# osh-2l-cpwg-via75-v2.net
KiCad netlist of a schematic drawn in EAGLE
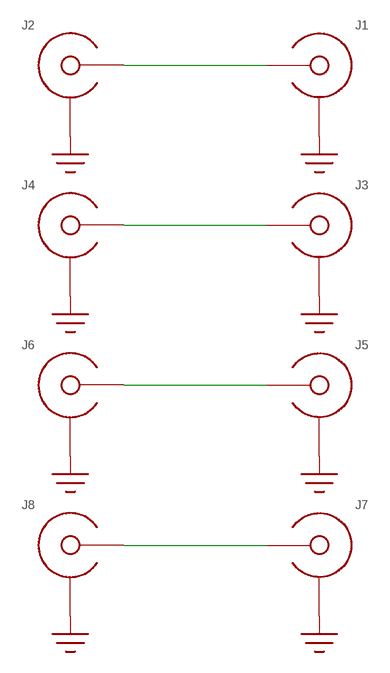
[diagram p0: schematic, sheet 1]

(export (version "E")
  (design (tool "Eeschema 10.0.6"))
  (components
    (comp (ref "J1")
      (value "SMA-EDGE-LAUNCH4020_TAPER")
      (footprint "eagle-import:SMA_EDGE_LAUNCH_2L_4020_TAPER")
      (libsource (lib "eagle-import") (part "SMA-EDGE-LAUNCH4020_TAPER"))
    )
    (comp (ref "J2")
      (value "SMA-EDGE-LAUNCH4020_TAPER")
      (footprint "eagle-import:SMA_EDGE_LAUNCH_2L_4020_TAPER")
      (libsource (lib "eagle-import") (part "yapo_SMA-EDGE-LAUNCH4020_TAPER"))
    )
    (comp (ref "J3")
      (value "SMA-EDGE-LAUNCH4020_TAPER")
      (footprint "eagle-import:SMA_EDGE_LAUNCH_2L_4020_TAPER")
      (libsource (lib "eagle-import") (part "SMA-EDGE-LAUNCH4020_TAPER"))
    )
    (comp (ref "J4")
      (value "SMA-EDGE-LAUNCH4020_TAPER")
      (footprint "eagle-import:SMA_EDGE_LAUNCH_2L_4020_TAPER")
      (libsource (lib "eagle-import") (part "yapo_SMA-EDGE-LAUNCH4020_TAPER"))
    )
    (comp (ref "J5")
      (value "SMA-EDGE-LAUNCH4020_TAPER")
      (footprint "eagle-import:SMA_EDGE_LAUNCH_2L_4020_TAPER")
      (libsource (lib "eagle-import") (part "SMA-EDGE-LAUNCH4020_TAPER"))
    )
    (comp (ref "J6")
      (value "SMA-EDGE-LAUNCH4020_TAPER")
      (footprint "eagle-import:SMA_EDGE_LAUNCH_2L_4020_TAPER")
      (libsource (lib "eagle-import") (part "yapo_SMA-EDGE-LAUNCH4020_TAPER"))
    )
    (comp (ref "J7")
      (value "SMA-EDGE-LAUNCH4020_TAPER")
      (footprint "eagle-import:SMA_EDGE_LAUNCH_2L_4020_TAPER")
      (libsource (lib "eagle-import") (part "SMA-EDGE-LAUNCH4020_TAPER"))
    )
    (comp (ref "J8")
      (value "SMA-EDGE-LAUNCH4020_TAPER")
      (footprint "eagle-import:SMA_EDGE_LAUNCH_2L_4020_TAPER")
      (libsource (lib "eagle-import") (part "yapo_SMA-EDGE-LAUNCH4020_TAPER"))
    )
  )
  (nets
    (net (code "1") (name "GND") (class "Default")
      (node (ref "J1") (pin "BOTTOM_GND") (pinfunction "SHIELD_BOTTOM_GND") (pintype "bidirectional"))
      (node (ref "J1") (pin "GND@1") (pinfunction "SHIELD_GND@1") (pintype "bidirectional"))
      (node (ref "J1") (pin "GND@14") (pinfunction "SHIELD_GND@14") (pintype "bidirectional"))
      (node (ref "J1") (pin "GND@15") (pinfunction "SHIELD_GND@15") (pintype "bidirectional"))
      (node (ref "J1") (pin "GND@16") (pinfunction "SHIELD_GND@16") (pintype "bidirectional"))
      (node (ref "J1") (pin "GND@17") (pinfunction "SHIELD_GND@17") (pintype "bidirectional"))
      (node (ref "J1") (pin "GND@2") (pinfunction "SHIELD_GND@2") (pintype "bidirectional"))
      (node (ref "J1") (pin "GND@3") (pinfunction "SHIELD_GND@3") (pintype "bidirectional"))
      (node (ref "J1") (pin "GND@4") (pinfunction "SHIELD_GND@4") (pintype "bidirectional"))
      (node (ref "J1") (pin "GND@5") (pinfunction "SHIELD_GND@5") (pintype "bidirectional"))
      (node (ref "J1") (pin "GND@6") (pinfunction "SHIELD_GND@6") (pintype "bidirectional"))
      (node (ref "J1") (pin "GND@7") (pinfunction "SHIELD_GND@7") (pintype "bidirectional"))
      (node (ref "J1") (pin "GND@8") (pinfunction "SHIELD_GND@8") (pintype "bidirectional"))
      (node (ref "J1") (pin "GND_PAD1") (pinfunction "SHIELD_GND_PAD1") (pintype "bidirectional"))
      (node (ref "J1") (pin "GND_PAD2") (pinfunction "SHIELD_GND_PAD2") (pintype "bidirectional"))
      (node (ref "J1") (pin "P$1") (pinfunction "SHIELD_P$1") (pintype "bidirectional"))
      (node (ref "J1") (pin "P$2") (pinfunction "SHIELD_P$2") (pintype "bidirectional"))
      (node (ref "J2") (pin "BOTTOM_GND") (pinfunction "SHIELD_BOTTOM_GND") (pintype "bidirectional"))
      (node (ref "J2") (pin "GND@1") (pinfunction "SHIELD_GND@1") (pintype "bidirectional"))
      (node (ref "J2") (pin "GND@14") (pinfunction "SHIELD_GND@14") (pintype "bidirectional"))
      (node (ref "J2") (pin "GND@15") (pinfunction "SHIELD_GND@15") (pintype "bidirectional"))
      (node (ref "J2") (pin "GND@16") (pinfunction "SHIELD_GND@16") (pintype "bidirectional"))
      (node (ref "J2") (pin "GND@17") (pinfunction "SHIELD_GND@17") (pintype "bidirectional"))
      (node (ref "J2") (pin "GND@2") (pinfunction "SHIELD_GND@2") (pintype "bidirectional"))
      (node (ref "J2") (pin "GND@3") (pinfunction "SHIELD_GND@3") (pintype "bidirectional"))
      (node (ref "J2") (pin "GND@4") (pinfunction "SHIELD_GND@4") (pintype "bidirectional"))
      (node (ref "J2") (pin "GND@5") (pinfunction "SHIELD_GND@5") (pintype "bidirectional"))
      (node (ref "J2") (pin "GND@6") (pinfunction "SHIELD_GND@6") (pintype "bidirectional"))
      (node (ref "J2") (pin "GND@7") (pinfunction "SHIELD_GND@7") (pintype "bidirectional"))
      (node (ref "J2") (pin "GND@8") (pinfunction "SHIELD_GND@8") (pintype "bidirectional"))
      (node (ref "J2") (pin "GND_PAD1") (pinfunction "SHIELD_GND_PAD1") (pintype "bidirectional"))
      (node (ref "J2") (pin "GND_PAD2") (pinfunction "SHIELD_GND_PAD2") (pintype "bidirectional"))
      (node (ref "J2") (pin "P$1") (pinfunction "SHIELD_P$1") (pintype "bidirectional"))
      (node (ref "J2") (pin "P$2") (pinfunction "SHIELD_P$2") (pintype "bidirectional"))
      (node (ref "J3") (pin "BOTTOM_GND") (pinfunction "SHIELD_BOTTOM_GND") (pintype "bidirectional"))
      (node (ref "J3") (pin "GND@1") (pinfunction "SHIELD_GND@1") (pintype "bidirectional"))
      (node (ref "J3") (pin "GND@14") (pinfunction "SHIELD_GND@14") (pintype "bidirectional"))
      (node (ref "J3") (pin "GND@15") (pinfunction "SHIELD_GND@15") (pintype "bidirectional"))
      (node (ref "J3") (pin "GND@16") (pinfunction "SHIELD_GND@16") (pintype "bidirectional"))
      (node (ref "J3") (pin "GND@17") (pinfunction "SHIELD_GND@17") (pintype "bidirectional"))
      (node (ref "J3") (pin "GND@2") (pinfunction "SHIELD_GND@2") (pintype "bidirectional"))
      (node (ref "J3") (pin "GND@3") (pinfunction "SHIELD_GND@3") (pintype "bidirectional"))
      (node (ref "J3") (pin "GND@4") (pinfunction "SHIELD_GND@4") (pintype "bidirectional"))
      (node (ref "J3") (pin "GND@5") (pinfunction "SHIELD_GND@5") (pintype "bidirectional"))
      (node (ref "J3") (pin "GND@6") (pinfunction "SHIELD_GND@6") (pintype "bidirectional"))
      (node (ref "J3") (pin "GND@7") (pinfunction "SHIELD_GND@7") (pintype "bidirectional"))
      (node (ref "J3") (pin "GND@8") (pinfunction "SHIELD_GND@8") (pintype "bidirectional"))
      (node (ref "J3") (pin "GND_PAD1") (pinfunction "SHIELD_GND_PAD1") (pintype "bidirectional"))
      (node (ref "J3") (pin "GND_PAD2") (pinfunction "SHIELD_GND_PAD2") (pintype "bidirectional"))
      (node (ref "J3") (pin "P$1") (pinfunction "SHIELD_P$1") (pintype "bidirectional"))
      (node (ref "J3") (pin "P$2") (pinfunction "SHIELD_P$2") (pintype "bidirectional"))
      (node (ref "J4") (pin "BOTTOM_GND") (pinfunction "SHIELD_BOTTOM_GND") (pintype "bidirectional"))
      (node (ref "J4") (pin "GND@1") (pinfunction "SHIELD_GND@1") (pintype "bidirectional"))
      (node (ref "J4") (pin "GND@14") (pinfunction "SHIELD_GND@14") (pintype "bidirectional"))
      (node (ref "J4") (pin "GND@15") (pinfunction "SHIELD_GND@15") (pintype "bidirectional"))
      (node (ref "J4") (pin "GND@16") (pinfunction "SHIELD_GND@16") (pintype "bidirectional"))
      (node (ref "J4") (pin "GND@17") (pinfunction "SHIELD_GND@17") (pintype "bidirectional"))
      (node (ref "J4") (pin "GND@2") (pinfunction "SHIELD_GND@2") (pintype "bidirectional"))
      (node (ref "J4") (pin "GND@3") (pinfunction "SHIELD_GND@3") (pintype "bidirectional"))
      (node (ref "J4") (pin "GND@4") (pinfunction "SHIELD_GND@4") (pintype "bidirectional"))
      (node (ref "J4") (pin "GND@5") (pinfunction "SHIELD_GND@5") (pintype "bidirectional"))
      (node (ref "J4") (pin "GND@6") (pinfunction "SHIELD_GND@6") (pintype "bidirectional"))
      (node (ref "J4") (pin "GND@7") (pinfunction "SHIELD_GND@7") (pintype "bidirectional"))
      (node (ref "J4") (pin "GND@8") (pinfunction "SHIELD_GND@8") (pintype "bidirectional"))
      (node (ref "J4") (pin "GND_PAD1") (pinfunction "SHIELD_GND_PAD1") (pintype "bidirectional"))
      (node (ref "J4") (pin "GND_PAD2") (pinfunction "SHIELD_GND_PAD2") (pintype "bidirectional"))
      (node (ref "J4") (pin "P$1") (pinfunction "SHIELD_P$1") (pintype "bidirectional"))
      (node (ref "J4") (pin "P$2") (pinfunction "SHIELD_P$2") (pintype "bidirectional"))
      (node (ref "J5") (pin "BOTTOM_GND") (pinfunction "SHIELD_BOTTOM_GND") (pintype "bidirectional"))
      (node (ref "J5") (pin "GND@1") (pinfunction "SHIELD_GND@1") (pintype "bidirectional"))
      (node (ref "J5") (pin "GND@14") (pinfunction "SHIELD_GND@14") (pintype "bidirectional"))
      (node (ref "J5") (pin "GND@15") (pinfunction "SHIELD_GND@15") (pintype "bidirectional"))
      (node (ref "J5") (pin "GND@16") (pinfunction "SHIELD_GND@16") (pintype "bidirectional"))
      (node (ref "J5") (pin "GND@17") (pinfunction "SHIELD_GND@17") (pintype "bidirectional"))
      (node (ref "J5") (pin "GND@2") (pinfunction "SHIELD_GND@2") (pintype "bidirectional"))
      (node (ref "J5") (pin "GND@3") (pinfunction "SHIELD_GND@3") (pintype "bidirectional"))
      (node (ref "J5") (pin "GND@4") (pinfunction "SHIELD_GND@4") (pintype "bidirectional"))
      (node (ref "J5") (pin "GND@5") (pinfunction "SHIELD_GND@5") (pintype "bidirectional"))
      (node (ref "J5") (pin "GND@6") (pinfunction "SHIELD_GND@6") (pintype "bidirectional"))
      (node (ref "J5") (pin "GND@7") (pinfunction "SHIELD_GND@7") (pintype "bidirectional"))
      (node (ref "J5") (pin "GND@8") (pinfunction "SHIELD_GND@8") (pintype "bidirectional"))
      (node (ref "J5") (pin "GND_PAD1") (pinfunction "SHIELD_GND_PAD1") (pintype "bidirectional"))
      (node (ref "J5") (pin "GND_PAD2") (pinfunction "SHIELD_GND_PAD2") (pintype "bidirectional"))
      (node (ref "J5") (pin "P$1") (pinfunction "SHIELD_P$1") (pintype "bidirectional"))
      (node (ref "J5") (pin "P$2") (pinfunction "SHIELD_P$2") (pintype "bidirectional"))
      (node (ref "J6") (pin "BOTTOM_GND") (pinfunction "SHIELD_BOTTOM_GND") (pintype "bidirectional"))
      (node (ref "J6") (pin "GND@1") (pinfunction "SHIELD_GND@1") (pintype "bidirectional"))
      (node (ref "J6") (pin "GND@14") (pinfunction "SHIELD_GND@14") (pintype "bidirectional"))
      (node (ref "J6") (pin "GND@15") (pinfunction "SHIELD_GND@15") (pintype "bidirectional"))
      (node (ref "J6") (pin "GND@16") (pinfunction "SHIELD_GND@16") (pintype "bidirectional"))
      (node (ref "J6") (pin "GND@17") (pinfunction "SHIELD_GND@17") (pintype "bidirectional"))
      (node (ref "J6") (pin "GND@2") (pinfunction "SHIELD_GND@2") (pintype "bidirectional"))
      (node (ref "J6") (pin "GND@3") (pinfunction "SHIELD_GND@3") (pintype "bidirectional"))
      (node (ref "J6") (pin "GND@4") (pinfunction "SHIELD_GND@4") (pintype "bidirectional"))
      (node (ref "J6") (pin "GND@5") (pinfunction "SHIELD_GND@5") (pintype "bidirectional"))
      (node (ref "J6") (pin "GND@6") (pinfunction "SHIELD_GND@6") (pintype "bidirectional"))
      (node (ref "J6") (pin "GND@7") (pinfunction "SHIELD_GND@7") (pintype "bidirectional"))
      (node (ref "J6") (pin "GND@8") (pinfunction "SHIELD_GND@8") (pintype "bidirectional"))
      (node (ref "J6") (pin "GND_PAD1") (pinfunction "SHIELD_GND_PAD1") (pintype "bidirectional"))
      (node (ref "J6") (pin "GND_PAD2") (pinfunction "SHIELD_GND_PAD2") (pintype "bidirectional"))
      (node (ref "J6") (pin "P$1") (pinfunction "SHIELD_P$1") (pintype "bidirectional"))
      (node (ref "J6") (pin "P$2") (pinfunction "SHIELD_P$2") (pintype "bidirectional"))
      (node (ref "J7") (pin "BOTTOM_GND") (pinfunction "SHIELD_BOTTOM_GND") (pintype "bidirectional"))
      (node (ref "J7") (pin "GND@1") (pinfunction "SHIELD_GND@1") (pintype "bidirectional"))
      (node (ref "J7") (pin "GND@14") (pinfunction "SHIELD_GND@14") (pintype "bidirectional"))
      (node (ref "J7") (pin "GND@15") (pinfunction "SHIELD_GND@15") (pintype "bidirectional"))
      (node (ref "J7") (pin "GND@16") (pinfunction "SHIELD_GND@16") (pintype "bidirectional"))
      (node (ref "J7") (pin "GND@17") (pinfunction "SHIELD_GND@17") (pintype "bidirectional"))
      (node (ref "J7") (pin "GND@2") (pinfunction "SHIELD_GND@2") (pintype "bidirectional"))
      (node (ref "J7") (pin "GND@3") (pinfunction "SHIELD_GND@3") (pintype "bidirectional"))
      (node (ref "J7") (pin "GND@4") (pinfunction "SHIELD_GND@4") (pintype "bidirectional"))
      (node (ref "J7") (pin "GND@5") (pinfunction "SHIELD_GND@5") (pintype "bidirectional"))
      (node (ref "J7") (pin "GND@6") (pinfunction "SHIELD_GND@6") (pintype "bidirectional"))
      (node (ref "J7") (pin "GND@7") (pinfunction "SHIELD_GND@7") (pintype "bidirectional"))
      (node (ref "J7") (pin "GND@8") (pinfunction "SHIELD_GND@8") (pintype "bidirectional"))
      (node (ref "J7") (pin "GND_PAD1") (pinfunction "SHIELD_GND_PAD1") (pintype "bidirectional"))
      (node (ref "J7") (pin "GND_PAD2") (pinfunction "SHIELD_GND_PAD2") (pintype "bidirectional"))
      (node (ref "J7") (pin "P$1") (pinfunction "SHIELD_P$1") (pintype "bidirectional"))
      (node (ref "J7") (pin "P$2") (pinfunction "SHIELD_P$2") (pintype "bidirectional"))
      (node (ref "J8") (pin "BOTTOM_GND") (pinfunction "SHIELD_BOTTOM_GND") (pintype "bidirectional"))
      (node (ref "J8") (pin "GND@1") (pinfunction "SHIELD_GND@1") (pintype "bidirectional"))
      (node (ref "J8") (pin "GND@14") (pinfunction "SHIELD_GND@14") (pintype "bidirectional"))
      (node (ref "J8") (pin "GND@15") (pinfunction "SHIELD_GND@15") (pintype "bidirectional"))
      (node (ref "J8") (pin "GND@16") (pinfunction "SHIELD_GND@16") (pintype "bidirectional"))
      (node (ref "J8") (pin "GND@17") (pinfunction "SHIELD_GND@17") (pintype "bidirectional"))
      (node (ref "J8") (pin "GND@2") (pinfunction "SHIELD_GND@2") (pintype "bidirectional"))
      (node (ref "J8") (pin "GND@3") (pinfunction "SHIELD_GND@3") (pintype "bidirectional"))
      (node (ref "J8") (pin "GND@4") (pinfunction "SHIELD_GND@4") (pintype "bidirectional"))
      (node (ref "J8") (pin "GND@5") (pinfunction "SHIELD_GND@5") (pintype "bidirectional"))
      (node (ref "J8") (pin "GND@6") (pinfunction "SHIELD_GND@6") (pintype "bidirectional"))
      (node (ref "J8") (pin "GND@7") (pinfunction "SHIELD_GND@7") (pintype "bidirectional"))
      (node (ref "J8") (pin "GND@8") (pinfunction "SHIELD_GND@8") (pintype "bidirectional"))
      (node (ref "J8") (pin "GND_PAD1") (pinfunction "SHIELD_GND_PAD1") (pintype "bidirectional"))
      (node (ref "J8") (pin "GND_PAD2") (pinfunction "SHIELD_GND_PAD2") (pintype "bidirectional"))
      (node (ref "J8") (pin "P$1") (pinfunction "SHIELD_P$1") (pintype "bidirectional"))
      (node (ref "J8") (pin "P$2") (pinfunction "SHIELD_P$2") (pintype "bidirectional"))
    )
    (net (code "2") (name "Net-(J1-CENTER)") (class "Default")
      (node (ref "J1") (pin "CENTER@1") (pinfunction "CENTER_CENTER@1") (pintype "bidirectional"))
      (node (ref "J2") (pin "CENTER@1") (pinfunction "CENTER_CENTER@1") (pintype "bidirectional"))
    )
    (net (code "3") (name "Net-(J3-CENTER)") (class "Default")
      (node (ref "J3") (pin "CENTER@1") (pinfunction "CENTER_CENTER@1") (pintype "bidirectional"))
      (node (ref "J4") (pin "CENTER@1") (pinfunction "CENTER_CENTER@1") (pintype "bidirectional"))
    )
    (net (code "4") (name "Net-(J5-CENTER)") (class "Default")
      (node (ref "J5") (pin "CENTER@1") (pinfunction "CENTER_CENTER@1") (pintype "bidirectional"))
      (node (ref "J6") (pin "CENTER@1") (pinfunction "CENTER_CENTER@1") (pintype "bidirectional"))
    )
    (net (code "5") (name "Net-(J7-CENTER)") (class "Default")
      (node (ref "J7") (pin "CENTER@1") (pinfunction "CENTER_CENTER@1") (pintype "bidirectional"))
      (node (ref "J8") (pin "CENTER@1") (pinfunction "CENTER_CENTER@1") (pintype "bidirectional"))
    )
  )
)
